# USB_fix.net
KiCad netlist of a schematic drawn in Altium Designer
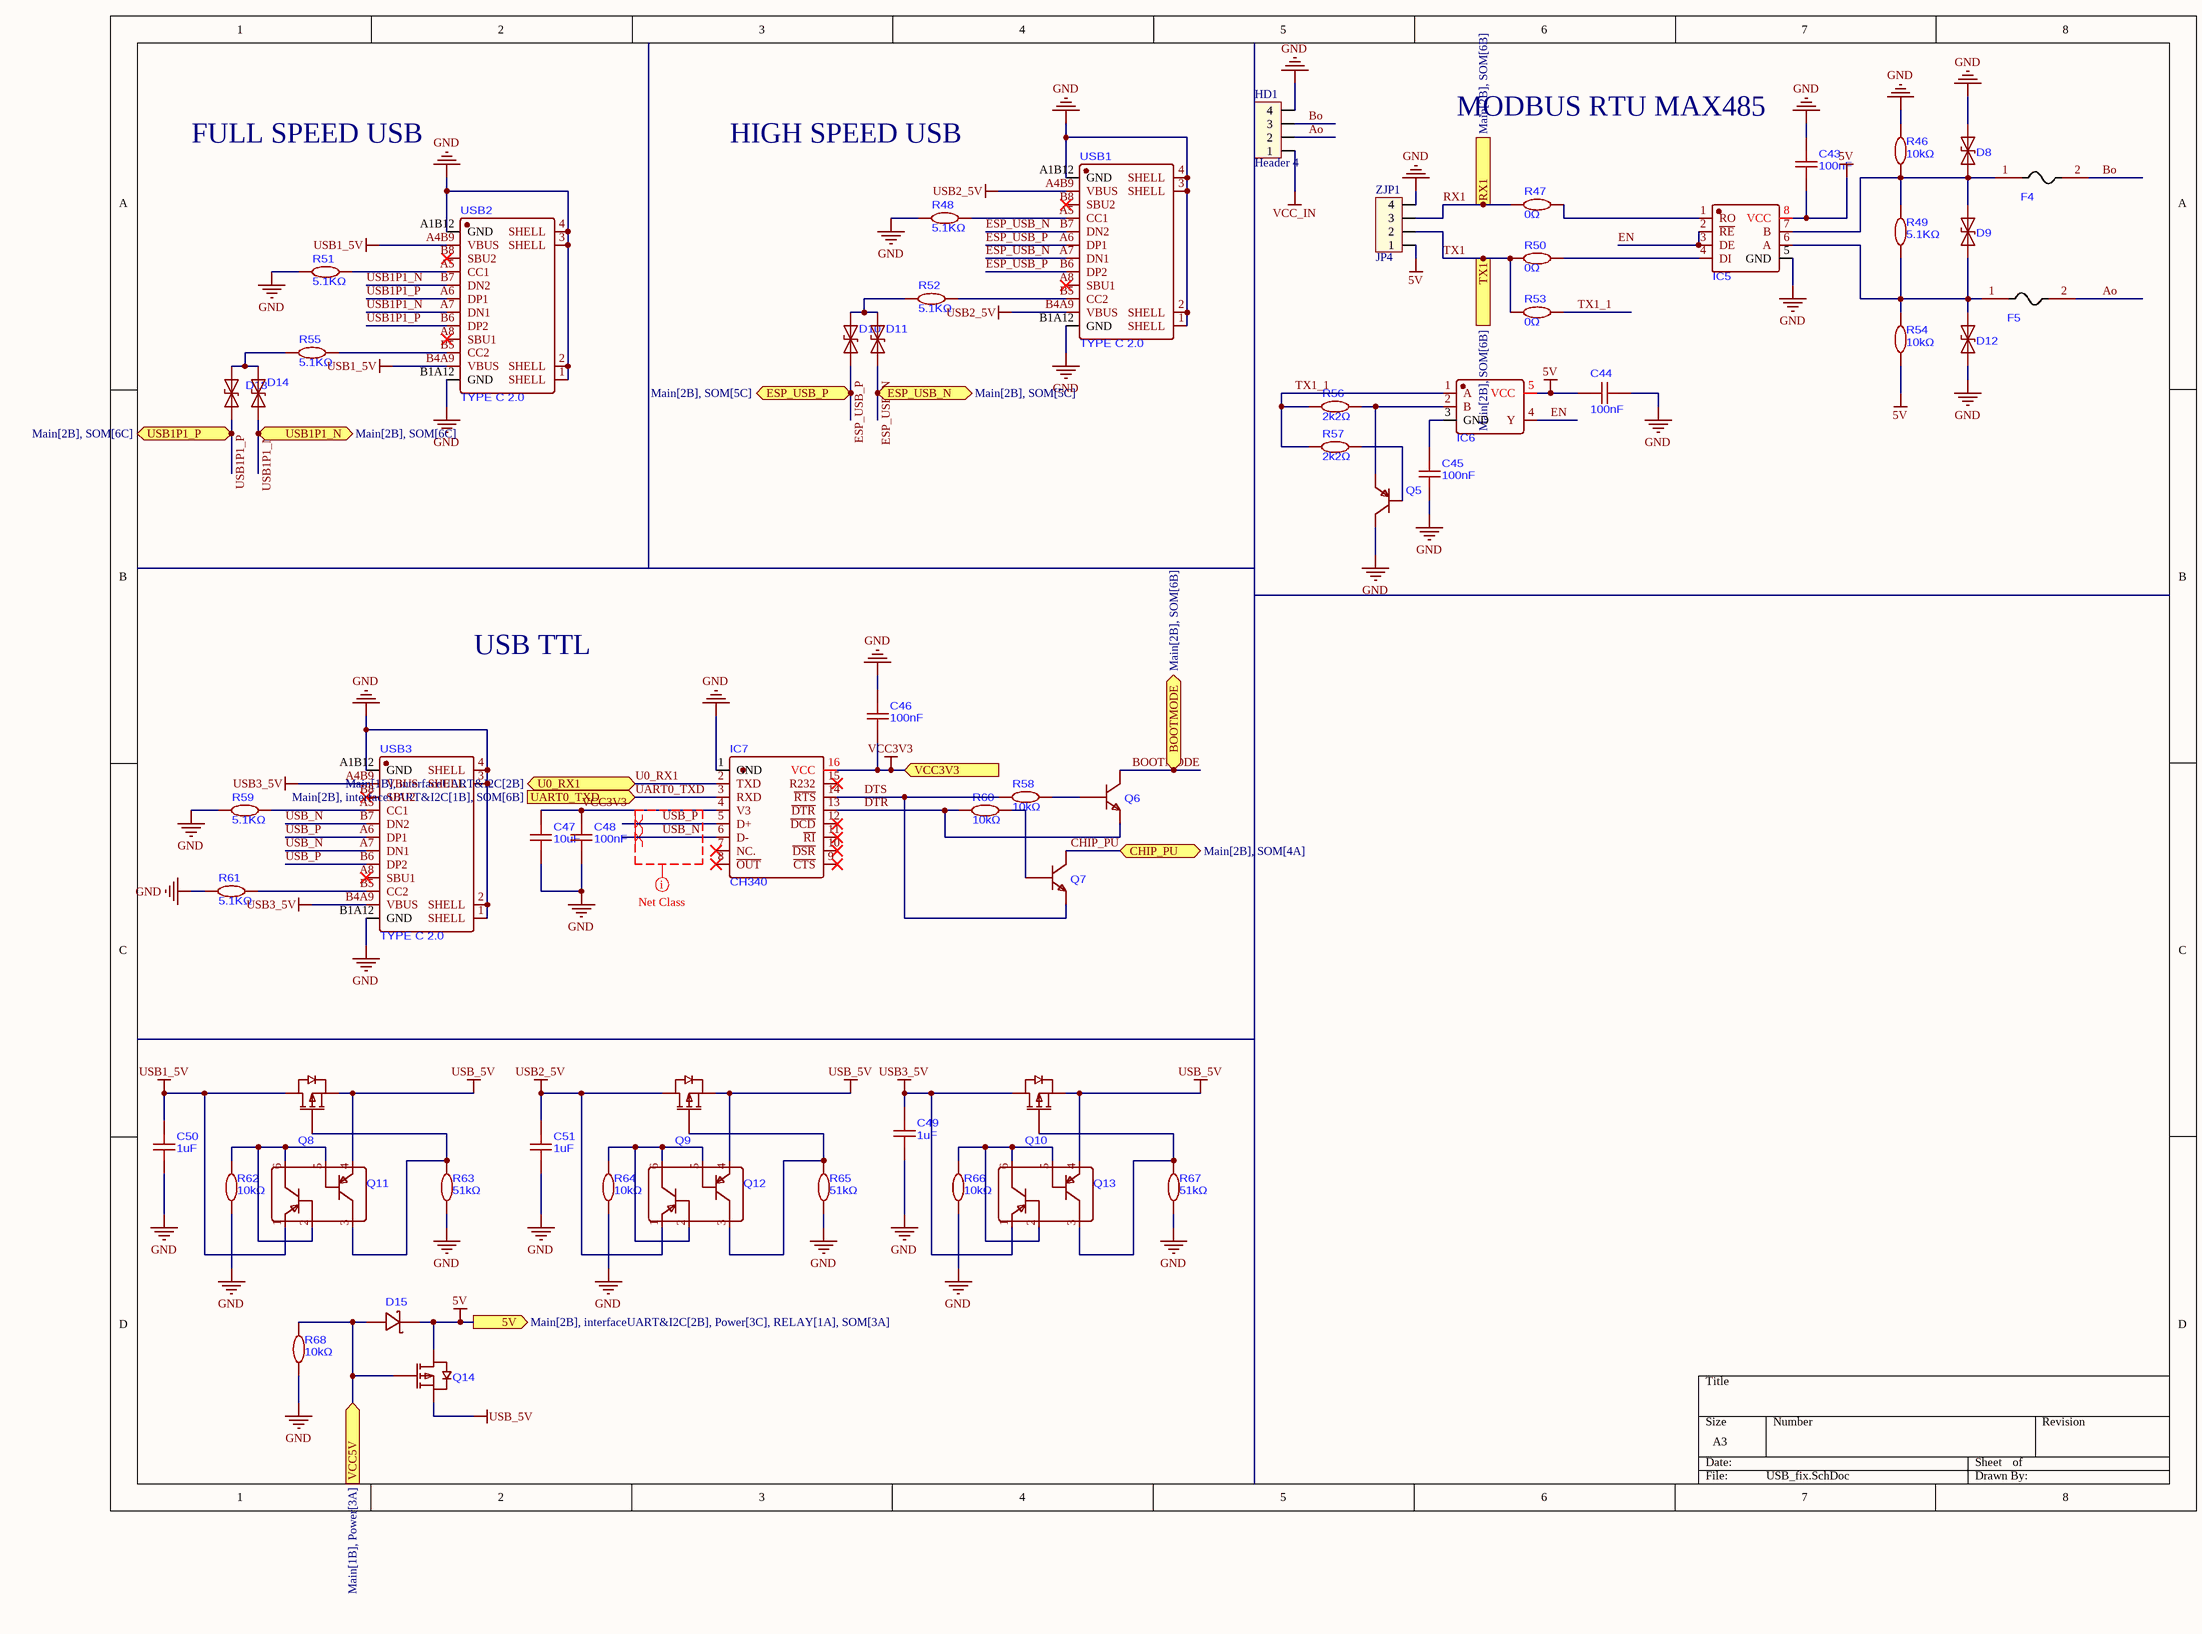
[diagram p0: USB_fix.SchDoc]

(export (version "E")
  (design (tool "Eeschema 10.0.6"))
  (components
    (comp (ref "C43")
      (value "100nF")
      (footprint "C0603")
      (description "50V 100nF X7R ±10% 0603 Ceramic Capacitors ROHS")
      (libsource (lib "Schlib2") (part "CC0603KRX7R9BB104"))
    )
    (comp (ref "C44")
      (value "100nF")
      (footprint "C0603")
      (description "50V 100nF X7R ±10% 0603 Ceramic Capacitors ROHS")
      (libsource (lib "Schlib2") (part "CC0603KRX7R9BB104"))
    )
    (comp (ref "C45")
      (value "100nF")
      (footprint "C0603")
      (description "50V 100nF X7R ±10% 0603 Ceramic Capacitors ROHS")
      (libsource (lib "Schlib2") (part "CC0603KRX7R9BB104"))
    )
    (comp (ref "C46")
      (value "100nF")
      (footprint "C0603")
      (description "50V 100nF X7R ±10% 0603 Ceramic Capacitors ROHS")
      (libsource (lib "Schlib2") (part "CC0603KRX7R9BB104"))
    )
    (comp (ref "C47")
      (value "10uF")
      (footprint "C0603")
      (description "25V 10uF X5R ±20% 0603 Ceramic Capacitors ROHS")
      (libsource (lib "Schlib2") (part "CL10A106MA8NRNC"))
    )
    (comp (ref "C48")
      (value "100nF")
      (footprint "C0603")
      (description "50V 100nF X7R ±10% 0603 Ceramic Capacitors ROHS")
      (libsource (lib "Schlib2") (part "CC0603KRX7R9BB104"))
    )
    (comp (ref "C49")
      (value "1uF")
      (footprint "C0603")
      (description "25V 1uF X7R ±10% 0603 Ceramic Capacitors ROHS")
      (libsource (lib "Schlib2") (part "CL10B105KA8NNNC"))
    )
    (comp (ref "C50")
      (value "1uF")
      (footprint "C0603")
      (description "25V 1uF X7R ±10% 0603 Ceramic Capacitors ROHS")
      (libsource (lib "Schlib2") (part "CL10B105KA8NNNC"))
    )
    (comp (ref "C51")
      (value "1uF")
      (footprint "C0603")
      (description "25V 1uF X7R ±10% 0603 Ceramic Capacitors ROHS")
      (libsource (lib "Schlib2") (part "CL10B105KA8NNNC"))
    )
    (comp (ref "D8")
      (value "TVS DIODE 5VWM 18.6VC SOD-523")
      (footprint "SOD-523_L1.2-W0.8-LS1.6-BI")
      (description "9.4A@8/20us 18.6V 7.8V 5V SOD-523 TVS Diodes RoHS")
      (libsource (lib "Schlib2") (part "LESD5D5.0CT1G"))
    )
    (comp (ref "D9")
      (value "TVS DIODE 5VWM 18.6VC SOD-523")
      (footprint "SOD-523_L1.2-W0.8-LS1.6-BI")
      (description "9.4A@8/20us 18.6V 7.8V 5V SOD-523 TVS Diodes RoHS")
      (libsource (lib "Schlib2") (part "LESD5D5.0CT1G"))
    )
    (comp (ref "D10")
      (value "TVS DIODE 5VWM 18.6VC SOD-523")
      (footprint "SOD-523_L1.2-W0.8-LS1.6-BI")
      (description "9.4A@8/20us 18.6V 7.8V 5V SOD-523 TVS Diodes RoHS")
      (libsource (lib "Schlib2") (part "LESD5D5.0CT1G"))
    )
    (comp (ref "D11")
      (value "TVS DIODE 5VWM 18.6VC SOD-523")
      (footprint "SOD-523_L1.2-W0.8-LS1.6-BI")
      (description "9.4A@8/20us 18.6V 7.8V 5V SOD-523 TVS Diodes RoHS")
      (libsource (lib "Schlib2") (part "LESD5D5.0CT1G"))
    )
    (comp (ref "D12")
      (value "TVS DIODE 5VWM 18.6VC SOD-523")
      (footprint "SOD-523_L1.2-W0.8-LS1.6-BI")
      (description "9.4A@8/20us 18.6V 7.8V 5V SOD-523 TVS Diodes RoHS")
      (libsource (lib "Schlib2") (part "LESD5D5.0CT1G"))
    )
    (comp (ref "D13")
      (value "TVS DIODE 5VWM 18.6VC SOD-523")
      (footprint "SOD-523_L1.2-W0.8-LS1.6-BI")
      (description "9.4A@8/20us 18.6V 7.8V 5V SOD-523 TVS Diodes RoHS")
      (libsource (lib "Schlib2") (part "LESD5D5.0CT1G"))
    )
    (comp (ref "D14")
      (value "TVS DIODE 5VWM 18.6VC SOD-523")
      (footprint "SOD-523_L1.2-W0.8-LS1.6-BI")
      (description "9.4A@8/20us 18.6V 7.8V 5V SOD-523 TVS Diodes RoHS")
      (libsource (lib "Schlib2") (part "LESD5D5.0CT1G"))
    )
    (comp (ref "D15")
      (value "B540CQ-13-F")
      (footprint "SMC_L6.9-W5.9-LS7.9-RD")
      (description "40V 550mV@5A 5A SMC(DO-214AB) Single Diodes ROHS")
      (libsource (lib "Schlib2") (part "B540CQ-13-F"))
    )
    (comp (ref "F4")
      (value "PTC RESET FUSE 24V 100mA 0603")
      (footprint "F0603")
      (description "24V 100mA 40A 300mA 900mΩ 0603 PTC Resettable Fuses RoHS")
      (libsource (lib "Schlib2") (part "0603-010-24V"))
    )
    (comp (ref "F5")
      (value "PTC RESET FUSE 24V 100mA 0603")
      (footprint "F0603")
      (description "24V 100mA 40A 300mA 900mΩ 0603 PTC Resettable Fuses RoHS")
      (libsource (lib "Schlib2") (part "0603-010-24V"))
    )
    (comp (ref "HD1")
      (value "Header 4")
      (footprint "HED4")
      (description "Header 4 (Green)")
      (libsource (lib "syhaunguyen") (part "Hed4"))
    )
    (comp (ref "IC5")
      (value "Low-Power, Slew-Rate-Limited RS-485/RS-422 Transceivers")
      (footprint "SOP-8_L4.9-W3.9-P1.27-LS6.0-BL")
      (description "Transceiver 4.75V~5.25V SOIC-8 Drivers, Receivers, Transceivers RoHS")
      (libsource (lib "Schlib2") (part "MAX485ESA+T_C41365333"))
    )
    (comp (ref "IC6")
      (value "SINGLE 2-INPUT NAND GATE WITH SCHMITT-TRIGGER INPUTS")
      (footprint "SOT-23-5_L3.0-W1.7-P0.95-LS2.8-BL")
      (description "5ns@5V,50pF 10uA 1.65V~5.5V NAND Gate SOT-23-5 Gates and Inverters RoHS")
      (libsource (lib "Schlib2") (part "TP74LVC1G132S5"))
    )
    (comp (ref "IC7")
      (value "CH340")
      (footprint "SOP-16_L10.0-W3.9-P1.27-LS6.0-BL")
      (description "Transceiver USB 2.0 SOP-16 Interface Controllers RoHS")
      (libsource (lib "Schlib2") (part "CH340C"))
    )
    (comp (ref "Q5")
      (value "TRANS PNP 25V 1.5A SOT-23")
      (footprint "SOT-23-3_L2.9-W1.3-P1.90-LS2.4-BR")
      (description "300mW 25V 1.5A PNP SOT-23 Single Bipolar Transistors RoHS")
      (libsource (lib "Schlib2") (part "SS8550_C7420371"))
    )
    (comp (ref "Q6")
      (value "TRANS NPN 25V 0.5A SOT-23")
      (footprint "SOT-23-3_L2.9-W1.3-P1.90-LS2.4-BR")
      (description "300mW 25V 500mA NPN SOT-23 Single Bipolar Transistors RoHS")
      (libsource (lib "Schlib2") (part "S8050_C2828466"))
    )
    (comp (ref "Q7")
      (value "TRANS NPN 25V 0.5A SOT-23")
      (footprint "SOT-23-3_L2.9-W1.3-P1.90-LS2.4-BR")
      (description "300mW 25V 500mA NPN SOT-23 Single Bipolar Transistors RoHS")
      (libsource (lib "Schlib2") (part "S8050_C2828466"))
    )
    (comp (ref "Q8")
      (value "MOSFET P-CH 30V 4.3A SOT-23")
      (footprint "SOT-23-3_L2.9-W1.6-P1.90-LS2.8-BR")
      (description "30V 4.3A 48mΩ@10V 2.5V@250uA 1 P-Channel SOT-23 Single FETs, MOSFETs ROHS")
      (libsource (lib "Schlib2") (part "AO3407A"))
    )
    (comp (ref "Q9")
      (value "MOSFET P-CH 30V 4.3A SOT-23")
      (footprint "SOT-23-3_L2.9-W1.6-P1.90-LS2.8-BR")
      (description "30V 4.3A 48mΩ@10V 2.5V@250uA 1 P-Channel SOT-23 Single FETs, MOSFETs ROHS")
      (libsource (lib "Schlib2") (part "AO3407A"))
    )
    (comp (ref "Q10")
      (value "MOSFET P-CH 30V 4.3A SOT-23")
      (footprint "SOT-23-3_L2.9-W1.6-P1.90-LS2.8-BR")
      (description "30V 4.3A 48mΩ@10V 2.5V@250uA 1 P-Channel SOT-23 Single FETs, MOSFETs ROHS")
      (libsource (lib "Schlib2") (part "AO3407A"))
    )
    (comp (ref "Q11")
      (value "TRANS PNP 40V 200mA SOT-363")
      (footprint "SC-70-6_L2.2-W1.3-P0.65-LS2.1-TL")
      (description "40V 150mW 200mA PNP SOT-363 Single Bipolar Transistors RoHS")
      (libsource (lib "Schlib2") (part "LMBT3906DW1T1"))
    )
    (comp (ref "Q12")
      (value "TRANS PNP 40V 200mA SOT-363")
      (footprint "SC-70-6_L2.2-W1.3-P0.65-LS2.1-TL")
      (description "40V 150mW 200mA PNP SOT-363 Single Bipolar Transistors RoHS")
      (libsource (lib "Schlib2") (part "LMBT3906DW1T1"))
    )
    (comp (ref "Q13")
      (value "TRANS PNP 40V 200mA SOT-363")
      (footprint "SC-70-6_L2.2-W1.3-P0.65-LS2.1-TL")
      (description "40V 150mW 200mA PNP SOT-363 Single Bipolar Transistors RoHS")
      (libsource (lib "Schlib2") (part "LMBT3906DW1T1"))
    )
    (comp (ref "Q14")
      (value "MOSFET P-CH 30V 4.3A SOT-23")
      (footprint "SOT-23-3_L2.9-W1.6-P1.90-LS2.8-BR")
      (description "30V 4.3A 48mΩ@10V 2.5V@250uA 1 P-Channel SOT-23 Single FETs, MOSFETs ROHS")
      (libsource (lib "Schlib2") (part "AO3407A"))
    )
    (comp (ref "R46")
      (value "10kΩ")
      (footprint "R0603")
      (description "100mW 10kΩ 75V ±100ppm/℃ Thick Film Resistor ±1% 0603 Chip Resistor - Surface Mount ROHS")
      (libsource (lib "Schlib2") (part "RC0603FR-0710KL"))
    )
    (comp (ref "R47")
      (value "0Ω")
      (footprint "R0603")
      (description "100mW 0Ω 75V Thick Film Resistor ±5% 0603 Chip Resistor - Surface Mount RoHS")
      (libsource (lib "Schlib2") (part "RC0603JR-070RL"))
    )
    (comp (ref "R48")
      (value "5.1KΩ")
      (footprint "R0603")
      (description "100mW 5.1kΩ 75V ±100ppm/℃ Thick Film Resistor ±1% 0603 Chip Resistor - Surface Mount RoHS")
      (libsource (lib "Schlib2") (part "FRC0603F5101TS"))
    )
    (comp (ref "R49")
      (value "5.1KΩ")
      (footprint "R0603")
      (description "100mW 5.1kΩ 75V ±100ppm/℃ Thick Film Resistor ±1% 0603 Chip Resistor - Surface Mount RoHS")
      (libsource (lib "Schlib2") (part "FRC0603F5101TS"))
    )
    (comp (ref "R50")
      (value "0Ω")
      (footprint "R0603")
      (description "100mW 0Ω 75V Thick Film Resistor ±5% 0603 Chip Resistor - Surface Mount RoHS")
      (libsource (lib "Schlib2") (part "RC0603JR-070RL"))
    )
    (comp (ref "R51")
      (value "5.1KΩ")
      (footprint "R0603")
      (description "100mW 5.1kΩ 75V ±100ppm/℃ Thick Film Resistor ±1% 0603 Chip Resistor - Surface Mount RoHS")
      (libsource (lib "Schlib2") (part "FRC0603F5101TS"))
    )
    (comp (ref "R52")
      (value "5.1KΩ")
      (footprint "R0603")
      (description "100mW 5.1kΩ 75V ±100ppm/℃ Thick Film Resistor ±1% 0603 Chip Resistor - Surface Mount RoHS")
      (libsource (lib "Schlib2") (part "FRC0603F5101TS"))
    )
    (comp (ref "R53")
      (value "0Ω")
      (footprint "R0603")
      (description "100mW 0Ω 75V Thick Film Resistor ±5% 0603 Chip Resistor - Surface Mount RoHS")
      (libsource (lib "Schlib2") (part "RC0603JR-070RL"))
    )
    (comp (ref "R54")
      (value "10kΩ")
      (footprint "R0603")
      (description "100mW 10kΩ 75V ±100ppm/℃ Thick Film Resistor ±1% 0603 Chip Resistor - Surface Mount ROHS")
      (libsource (lib "Schlib2") (part "RC0603FR-0710KL"))
    )
    (comp (ref "R55")
      (value "5.1KΩ")
      (footprint "R0603")
      (description "100mW 5.1kΩ 75V ±100ppm/℃ Thick Film Resistor ±1% 0603 Chip Resistor - Surface Mount RoHS")
      (libsource (lib "Schlib2") (part "FRC0603F5101TS"))
    )
    (comp (ref "R56")
      (value "2k2Ω")
      (footprint "R0603")
      (description "100mW 2.2kΩ 75V ±100ppm/℃ Thick Film Resistor ±1% 0603 Chip Resistor - Surface Mount RoHS")
      (libsource (lib "Schlib2") (part "RC0603FR-072K2L"))
    )
    (comp (ref "R57")
      (value "2k2Ω")
      (footprint "R0603")
      (description "100mW 2.2kΩ 75V ±100ppm/℃ Thick Film Resistor ±1% 0603 Chip Resistor - Surface Mount RoHS")
      (libsource (lib "Schlib2") (part "RC0603FR-072K2L"))
    )
    (comp (ref "R58")
      (value "10kΩ")
      (footprint "R0603")
      (description "100mW 10kΩ 75V ±100ppm/℃ Thick Film Resistor ±1% 0603 Chip Resistor - Surface Mount ROHS")
      (libsource (lib "Schlib2") (part "RC0603FR-0710KL"))
    )
    (comp (ref "R59")
      (value "5.1KΩ")
      (footprint "R0603")
      (description "100mW 5.1kΩ 75V ±100ppm/℃ Thick Film Resistor ±1% 0603 Chip Resistor - Surface Mount RoHS")
      (libsource (lib "Schlib2") (part "FRC0603F5101TS"))
    )
    (comp (ref "R60")
      (value "10kΩ")
      (footprint "R0603")
      (description "100mW 10kΩ 75V ±100ppm/℃ Thick Film Resistor ±1% 0603 Chip Resistor - Surface Mount ROHS")
      (libsource (lib "Schlib2") (part "RC0603FR-0710KL"))
    )
    (comp (ref "R61")
      (value "5.1KΩ")
      (footprint "R0603")
      (description "100mW 5.1kΩ 75V ±100ppm/℃ Thick Film Resistor ±1% 0603 Chip Resistor - Surface Mount RoHS")
      (libsource (lib "Schlib2") (part "FRC0603F5101TS"))
    )
    (comp (ref "R62")
      (value "10kΩ")
      (footprint "R0603")
      (description "100mW 10kΩ 75V ±100ppm/℃ Thick Film Resistor ±1% 0603 Chip Resistor - Surface Mount ROHS")
      (libsource (lib "Schlib2") (part "RC0603FR-0710KL"))
    )
    (comp (ref "R63")
      (value "51kΩ")
      (footprint "R0603")
      (description "100mW 51kΩ 75V ±100ppm/℃ Thick Film Resistor ±1% 0603 Chip Resistor - Surface Mount RoHS")
      (libsource (lib "Schlib2") (part "RC0603FR-07100KL_1RC0603FR-0751KL"))
    )
    (comp (ref "R64")
      (value "10kΩ")
      (footprint "R0603")
      (description "100mW 10kΩ 75V ±100ppm/℃ Thick Film Resistor ±1% 0603 Chip Resistor - Surface Mount ROHS")
      (libsource (lib "Schlib2") (part "RC0603FR-0710KL"))
    )
    (comp (ref "R65")
      (value "51kΩ")
      (footprint "R0603")
      (description "100mW 51kΩ 75V ±100ppm/℃ Thick Film Resistor ±1% 0603 Chip Resistor - Surface Mount RoHS")
      (libsource (lib "Schlib2") (part "RC0603FR-07100KL_1RC0603FR-0751KL"))
    )
    (comp (ref "R66")
      (value "10kΩ")
      (footprint "R0603")
      (description "100mW 10kΩ 75V ±100ppm/℃ Thick Film Resistor ±1% 0603 Chip Resistor - Surface Mount ROHS")
      (libsource (lib "Schlib2") (part "RC0603FR-0710KL"))
    )
    (comp (ref "R67")
      (value "51kΩ")
      (footprint "R0603")
      (description "100mW 51kΩ 75V ±100ppm/℃ Thick Film Resistor ±1% 0603 Chip Resistor - Surface Mount RoHS")
      (libsource (lib "Schlib2") (part "RC0603FR-07100KL_1RC0603FR-0751KL"))
    )
    (comp (ref "R68")
      (value "10kΩ")
      (footprint "R0603")
      (description "100mW 10kΩ 75V ±100ppm/℃ Thick Film Resistor ±1% 0603 Chip Resistor - Surface Mount ROHS")
      (libsource (lib "Schlib2") (part "RC0603FR-0710KL"))
    )
    (comp (ref "USB1")
      (value "TYPE C 2.0")
      (footprint "USB-C-SMD_G-SWITCH_GT-USB-7010ASV")
      (description "USB 2.0 1 16P -40℃~+85℃ Type-C SMD USB, DVI, HDMI Connector Assemblies RoHS")
      (libsource (lib "Schlib2") (part "GT-USB-7010ASV"))
    )
    (comp (ref "USB2")
      (value "TYPE C 2.0")
      (footprint "USB-C-SMD_G-SWITCH_GT-USB-7010ASV")
      (description "USB 2.0 1 16P -40℃~+85℃ Type-C SMD USB, DVI, HDMI Connector Assemblies RoHS")
      (libsource (lib "Schlib2") (part "GT-USB-7010ASV"))
    )
    (comp (ref "USB3")
      (value "TYPE C 2.0")
      (footprint "USB-C-SMD_G-SWITCH_GT-USB-7010ASV")
      (description "USB 2.0 1 16P -40℃~+85℃ Type-C SMD USB, DVI, HDMI Connector Assemblies RoHS")
      (libsource (lib "Schlib2") (part "GT-USB-7010ASV"))
    )
    (comp (ref "ZJP1")
      (value "JP4")
      (footprint "CON4")
      (description "Connector 4")
      (libsource (lib "syhaunguyen") (part "Con4"))
    )
  )
  (nets
    (net (code "1") (name "/Ao") (class "Default")
      (node (ref "F5") (pin "2") (pinfunction "2_2") (pintype "passive"))
      (node (ref "HD1") (pin "2") (pinfunction "2_2") (pintype "passive"))
    )
    (net (code "2") (name "/BOOTMODE") (class "Default")
      (node (ref "Q6") (pin "3") (pinfunction "C_3") (pintype "passive"))
    )
    (net (code "3") (name "/Bo") (class "Default")
      (node (ref "F4") (pin "2") (pinfunction "2_2") (pintype "passive"))
      (node (ref "HD1") (pin "3") (pinfunction "3_3") (pintype "passive"))
    )
    (net (code "4") (name "/CHIP_PU") (class "Default")
      (node (ref "Q7") (pin "3") (pinfunction "C_3") (pintype "passive"))
    )
    (net (code "5") (name "/DTR") (class "Default")
      (node (ref "IC7") (pin "13") (pinfunction "~{DTR}_13") (pintype "passive"))
      (node (ref "Q6") (pin "2") (pinfunction "E_2") (pintype "passive"))
      (node (ref "R60") (pin "1") (pinfunction "1_1") (pintype "passive"))
    )
    (net (code "6") (name "/DTS") (class "Default")
      (node (ref "IC7") (pin "14") (pinfunction "~{RTS}_14") (pintype "passive"))
      (node (ref "Q7") (pin "2") (pinfunction "E_2") (pintype "passive"))
      (node (ref "R58") (pin "1") (pinfunction "1_1") (pintype "passive"))
    )
    (net (code "7") (name "/EN") (class "Default")
      (node (ref "IC5") (pin "2") (pinfunction "~{RE}_2") (pintype "passive"))
      (node (ref "IC5") (pin "3") (pinfunction "DE_3") (pintype "passive"))
      (node (ref "IC6") (pin "4") (pinfunction "Y_4") (pintype "passive"))
    )
    (net (code "8") (name "/ESP_USB_N") (class "Default")
      (node (ref "D11") (pin "1") (pinfunction "K_1") (pintype "passive"))
      (node (ref "USB1") (pin "A7") (pinfunction "DN1_A7") (pintype "passive"))
      (node (ref "USB1") (pin "B7") (pinfunction "DN2_B7") (pintype "passive"))
    )
    (net (code "9") (name "/ESP_USB_P") (class "Default")
      (node (ref "D10") (pin "1") (pinfunction "K_1") (pintype "passive"))
      (node (ref "USB1") (pin "A6") (pinfunction "DP1_A6") (pintype "passive"))
      (node (ref "USB1") (pin "B6") (pinfunction "DP2_B6") (pintype "passive"))
    )
    (net (code "10") (name "/RX1") (class "Default")
      (node (ref "R47") (pin "1") (pinfunction "1_1") (pintype "passive"))
      (node (ref "ZJP1") (pin "3") (pinfunction "3_3") (pintype "passive"))
    )
    (net (code "11") (name "/TX1") (class "Default")
      (node (ref "R50") (pin "1") (pinfunction "1_1") (pintype "passive"))
      (node (ref "R53") (pin "1") (pinfunction "1_1") (pintype "passive"))
      (node (ref "ZJP1") (pin "2") (pinfunction "2_2") (pintype "passive"))
    )
    (net (code "12") (name "/TX1_1") (class "Default")
      (node (ref "IC6") (pin "1") (pinfunction "A_1") (pintype "passive"))
      (node (ref "R53") (pin "2") (pinfunction "2_2") (pintype "passive"))
      (node (ref "R56") (pin "2") (pinfunction "2_2") (pintype "passive"))
      (node (ref "R57") (pin "1") (pinfunction "1_1") (pintype "passive"))
    )
    (net (code "13") (name "/U0_RX1") (class "Default")
      (node (ref "IC7") (pin "2") (pinfunction "TXD_2") (pintype "passive"))
    )
    (net (code "14") (name "/UART0_TXD") (class "Default")
      (node (ref "IC7") (pin "3") (pinfunction "RXD_3") (pintype "passive"))
    )
    (net (code "15") (name "/USB1P1_N") (class "Default")
      (node (ref "D14") (pin "1") (pinfunction "K_1") (pintype "passive"))
      (node (ref "USB2") (pin "A7") (pinfunction "DN1_A7") (pintype "passive"))
      (node (ref "USB2") (pin "B7") (pinfunction "DN2_B7") (pintype "passive"))
    )
    (net (code "16") (name "/USB1P1_P") (class "Default")
      (node (ref "D13") (pin "1") (pinfunction "K_1") (pintype "passive"))
      (node (ref "USB2") (pin "A6") (pinfunction "DP1_A6") (pintype "passive"))
      (node (ref "USB2") (pin "B6") (pinfunction "DP2_B6") (pintype "passive"))
    )
    (net (code "17") (name "/USB_N") (class "Default")
      (node (ref "IC7") (pin "6") (pinfunction "D-_6") (pintype "passive"))
      (node (ref "USB3") (pin "A7") (pinfunction "DN1_A7") (pintype "passive"))
      (node (ref "USB3") (pin "B7") (pinfunction "DN2_B7") (pintype "passive"))
    )
    (net (code "18") (name "/USB_P") (class "Default")
      (node (ref "IC7") (pin "5") (pinfunction "D+_5") (pintype "passive"))
      (node (ref "USB3") (pin "A6") (pinfunction "DP1_A6") (pintype "passive"))
      (node (ref "USB3") (pin "B6") (pinfunction "DP2_B6") (pintype "passive"))
    )
    (net (code "19") (name "/VCC5V") (class "Default")
      (node (ref "D15") (pin "2") (pinfunction "A_2") (pintype "passive"))
      (node (ref "Q14") (pin "1") (pinfunction "G_1") (pintype "passive"))
      (node (ref "R68") (pin "2") (pinfunction "2_2") (pintype "passive"))
    )
    (net (code "20") (name "5V") (class "Default")
      (node (ref "C43") (pin "1") (pinfunction "1_1") (pintype "passive"))
      (node (ref "C44") (pin "2") (pinfunction "2_2") (pintype "passive"))
      (node (ref "D15") (pin "1") (pinfunction "C_1") (pintype "passive"))
      (node (ref "IC5") (pin "8") (pinfunction "VCC_8") (pintype "passive"))
      (node (ref "IC6") (pin "5") (pinfunction "VCC_5") (pintype "passive"))
      (node (ref "Q14") (pin "3") (pinfunction "D_3") (pintype "passive"))
      (node (ref "R54") (pin "1") (pinfunction "1_1") (pintype "passive"))
      (node (ref "ZJP1") (pin "1") (pinfunction "1_1") (pintype "passive"))
    )
    (net (code "21") (name "GND") (class "Default")
      (node (ref "C43") (pin "2") (pinfunction "2_2") (pintype "passive"))
      (node (ref "C44") (pin "1") (pinfunction "1_1") (pintype "passive"))
      (node (ref "C45") (pin "1") (pinfunction "1_1") (pintype "passive"))
      (node (ref "C46") (pin "2") (pinfunction "2_2") (pintype "passive"))
      (node (ref "C47") (pin "1") (pinfunction "1_1") (pintype "passive"))
      (node (ref "C48") (pin "1") (pinfunction "1_1") (pintype "passive"))
      (node (ref "C49") (pin "1") (pinfunction "1_1") (pintype "passive"))
      (node (ref "C50") (pin "1") (pinfunction "1_1") (pintype "passive"))
      (node (ref "C51") (pin "1") (pinfunction "1_1") (pintype "passive"))
      (node (ref "D12") (pin "1") (pinfunction "K_1") (pintype "passive"))
      (node (ref "D8") (pin "2") (pinfunction "A_2") (pintype "passive"))
      (node (ref "HD1") (pin "4") (pinfunction "4_4") (pintype "passive"))
      (node (ref "IC5") (pin "5") (pinfunction "GND_5") (pintype "passive"))
      (node (ref "IC7") (pin "1") (pinfunction "GND_1") (pintype "passive"))
      (node (ref "Q5") (pin "3") (pinfunction "C_3") (pintype "passive"))
      (node (ref "R46") (pin "2") (pinfunction "2_2") (pintype "passive"))
      (node (ref "R48") (pin "1") (pinfunction "1_1") (pintype "passive"))
      (node (ref "R51") (pin "1") (pinfunction "1_1") (pintype "passive"))
      (node (ref "R59") (pin "1") (pinfunction "1_1") (pintype "passive"))
      (node (ref "R61") (pin "1") (pinfunction "1_1") (pintype "passive"))
      (node (ref "R62") (pin "1") (pinfunction "1_1") (pintype "passive"))
      (node (ref "R63") (pin "1") (pinfunction "1_1") (pintype "passive"))
      (node (ref "R64") (pin "1") (pinfunction "1_1") (pintype "passive"))
      (node (ref "R65") (pin "1") (pinfunction "1_1") (pintype "passive"))
      (node (ref "R66") (pin "1") (pinfunction "1_1") (pintype "passive"))
      (node (ref "R67") (pin "1") (pinfunction "1_1") (pintype "passive"))
      (node (ref "R68") (pin "1") (pinfunction "1_1") (pintype "passive"))
      (node (ref "USB1") (pin "1") (pinfunction "SHELL_1") (pintype "passive"))
      (node (ref "USB1") (pin "2") (pinfunction "SHELL_2") (pintype "passive"))
      (node (ref "USB1") (pin "3") (pinfunction "SHELL_3") (pintype "passive"))
      (node (ref "USB1") (pin "4") (pinfunction "SHELL_4") (pintype "passive"))
      (node (ref "USB1") (pin "A1B12") (pinfunction "GND_A1B12") (pintype "passive"))
      (node (ref "USB1") (pin "B1A12") (pinfunction "GND_B1A12") (pintype "passive"))
      (node (ref "USB2") (pin "1") (pinfunction "SHELL_1") (pintype "passive"))
      (node (ref "USB2") (pin "2") (pinfunction "SHELL_2") (pintype "passive"))
      (node (ref "USB2") (pin "3") (pinfunction "SHELL_3") (pintype "passive"))
      (node (ref "USB2") (pin "4") (pinfunction "SHELL_4") (pintype "passive"))
      (node (ref "USB2") (pin "A1B12") (pinfunction "GND_A1B12") (pintype "passive"))
      (node (ref "USB2") (pin "B1A12") (pinfunction "GND_B1A12") (pintype "passive"))
      (node (ref "USB3") (pin "1") (pinfunction "SHELL_1") (pintype "passive"))
      (node (ref "USB3") (pin "2") (pinfunction "SHELL_2") (pintype "passive"))
      (node (ref "USB3") (pin "3") (pinfunction "SHELL_3") (pintype "passive"))
      (node (ref "USB3") (pin "4") (pinfunction "SHELL_4") (pintype "passive"))
      (node (ref "USB3") (pin "A1B12") (pinfunction "GND_A1B12") (pintype "passive"))
      (node (ref "USB3") (pin "B1A12") (pinfunction "GND_B1A12") (pintype "passive"))
      (node (ref "ZJP1") (pin "4") (pinfunction "4_4") (pintype "passive"))
    )
    (net (code "22") (name "Net-(D8-K)") (class "Default")
      (node (ref "D8") (pin "1") (pinfunction "K_1") (pintype "passive"))
      (node (ref "D9") (pin "2") (pinfunction "A_2") (pintype "passive"))
      (node (ref "F4") (pin "1") (pinfunction "1_1") (pintype "passive"))
      (node (ref "IC5") (pin "7") (pinfunction "B_7") (pintype "passive"))
      (node (ref "R46") (pin "1") (pinfunction "1_1") (pintype "passive"))
      (node (ref "R49") (pin "2") (pinfunction "2_2") (pintype "passive"))
    )
    (net (code "23") (name "Net-(D10-A)") (class "Default")
      (node (ref "D10") (pin "2") (pinfunction "A_2") (pintype "passive"))
      (node (ref "D11") (pin "2") (pinfunction "A_2") (pintype "passive"))
      (node (ref "R52") (pin "1") (pinfunction "1_1") (pintype "passive"))
    )
    (net (code "24") (name "Net-(D12-A)") (class "Default")
      (node (ref "D12") (pin "2") (pinfunction "A_2") (pintype "passive"))
      (node (ref "D9") (pin "1") (pinfunction "K_1") (pintype "passive"))
      (node (ref "F5") (pin "1") (pinfunction "1_1") (pintype "passive"))
      (node (ref "IC5") (pin "6") (pinfunction "A_6") (pintype "passive"))
      (node (ref "R49") (pin "1") (pinfunction "1_1") (pintype "passive"))
      (node (ref "R54") (pin "2") (pinfunction "2_2") (pintype "passive"))
    )
    (net (code "25") (name "Net-(D13-A)") (class "Default")
      (node (ref "D13") (pin "2") (pinfunction "A_2") (pintype "passive"))
      (node (ref "D14") (pin "2") (pinfunction "A_2") (pintype "passive"))
      (node (ref "R55") (pin "1") (pinfunction "1_1") (pintype "passive"))
    )
    (net (code "26") (name "Net-(IC5-DI)") (class "Default")
      (node (ref "IC5") (pin "4") (pinfunction "DI_4") (pintype "passive"))
      (node (ref "R50") (pin "2") (pinfunction "2_2") (pintype "passive"))
    )
    (net (code "27") (name "Net-(IC5-RO)") (class "Default")
      (node (ref "IC5") (pin "1") (pinfunction "RO_1") (pintype "passive"))
      (node (ref "R47") (pin "2") (pinfunction "2_2") (pintype "passive"))
    )
    (net (code "28") (name "Net-(IC6-B)") (class "Default")
      (node (ref "IC6") (pin "2") (pinfunction "B_2") (pintype "passive"))
      (node (ref "Q5") (pin "2") (pinfunction "E_2") (pintype "passive"))
      (node (ref "R56") (pin "1") (pinfunction "1_1") (pintype "passive"))
    )
    (net (code "29") (name "Net-(IC6-GND)") (class "Default")
      (node (ref "C45") (pin "2") (pinfunction "2_2") (pintype "passive"))
      (node (ref "IC6") (pin "3") (pinfunction "GND_3") (pintype "passive"))
    )
    (net (code "30") (name "Net-(Q5-B)") (class "Default")
      (node (ref "Q5") (pin "1") (pinfunction "B_1") (pintype "passive"))
      (node (ref "R57") (pin "2") (pinfunction "2_2") (pintype "passive"))
    )
    (net (code "31") (name "Net-(Q6-B)") (class "Default")
      (node (ref "Q6") (pin "1") (pinfunction "B_1") (pintype "passive"))
      (node (ref "R58") (pin "2") (pinfunction "2_2") (pintype "passive"))
    )
    (net (code "32") (name "Net-(Q7-B)") (class "Default")
      (node (ref "Q7") (pin "1") (pinfunction "B_1") (pintype "passive"))
      (node (ref "R60") (pin "2") (pinfunction "2_2") (pintype "passive"))
    )
    (net (code "33") (name "Net-(Q10-G)") (class "Default")
      (node (ref "Q10") (pin "1") (pinfunction "G_1") (pintype "passive"))
      (node (ref "Q13") (pin "3") (pinfunction "C1_3") (pintype "passive"))
      (node (ref "R67") (pin "2") (pinfunction "2_2") (pintype "passive"))
    )
    (net (code "34") (name "Net-(Q11-B1)") (class "Default")
      (node (ref "Q11") (pin "2") (pinfunction "B2_2") (pintype "passive"))
      (node (ref "Q11") (pin "5") (pinfunction "B1_5") (pintype "passive"))
      (node (ref "Q11") (pin "6") (pinfunction "C2_6") (pintype "passive"))
      (node (ref "R62") (pin "2") (pinfunction "2_2") (pintype "passive"))
    )
    (net (code "35") (name "Net-(Q11-C1)") (class "Default")
      (node (ref "Q11") (pin "3") (pinfunction "C1_3") (pintype "passive"))
      (node (ref "Q8") (pin "1") (pinfunction "G_1") (pintype "passive"))
      (node (ref "R63") (pin "2") (pinfunction "2_2") (pintype "passive"))
    )
    (net (code "36") (name "Net-(Q12-B1)") (class "Default")
      (node (ref "Q12") (pin "2") (pinfunction "B2_2") (pintype "passive"))
      (node (ref "Q12") (pin "5") (pinfunction "B1_5") (pintype "passive"))
      (node (ref "Q12") (pin "6") (pinfunction "C2_6") (pintype "passive"))
      (node (ref "R64") (pin "2") (pinfunction "2_2") (pintype "passive"))
    )
    (net (code "37") (name "Net-(Q12-C1)") (class "Default")
      (node (ref "Q12") (pin "3") (pinfunction "C1_3") (pintype "passive"))
      (node (ref "Q9") (pin "1") (pinfunction "G_1") (pintype "passive"))
      (node (ref "R65") (pin "2") (pinfunction "2_2") (pintype "passive"))
    )
    (net (code "38") (name "Net-(Q13-B1)") (class "Default")
      (node (ref "Q13") (pin "2") (pinfunction "B2_2") (pintype "passive"))
      (node (ref "Q13") (pin "5") (pinfunction "B1_5") (pintype "passive"))
      (node (ref "Q13") (pin "6") (pinfunction "C2_6") (pintype "passive"))
      (node (ref "R66") (pin "2") (pinfunction "2_2") (pintype "passive"))
    )
    (net (code "39") (name "Net-(USB1-CC1)") (class "Default")
      (node (ref "R48") (pin "2") (pinfunction "2_2") (pintype "passive"))
      (node (ref "USB1") (pin "A5") (pinfunction "CC1_A5") (pintype "passive"))
    )
    (net (code "40") (name "Net-(USB1-CC2)") (class "Default")
      (node (ref "R52") (pin "2") (pinfunction "2_2") (pintype "passive"))
      (node (ref "USB1") (pin "B5") (pinfunction "CC2_B5") (pintype "passive"))
    )
    (net (code "41") (name "Net-(USB2-CC1)") (class "Default")
      (node (ref "R51") (pin "2") (pinfunction "2_2") (pintype "passive"))
      (node (ref "USB2") (pin "A5") (pinfunction "CC1_A5") (pintype "passive"))
    )
    (net (code "42") (name "Net-(USB2-CC2)") (class "Default")
      (node (ref "R55") (pin "2") (pinfunction "2_2") (pintype "passive"))
      (node (ref "USB2") (pin "B5") (pinfunction "CC2_B5") (pintype "passive"))
    )
    (net (code "43") (name "Net-(USB3-CC1)") (class "Default")
      (node (ref "R59") (pin "2") (pinfunction "2_2") (pintype "passive"))
      (node (ref "USB3") (pin "A5") (pinfunction "CC1_A5") (pintype "passive"))
    )
    (net (code "44") (name "Net-(USB3-CC2)") (class "Default")
      (node (ref "R61") (pin "2") (pinfunction "2_2") (pintype "passive"))
      (node (ref "USB3") (pin "B5") (pinfunction "CC2_B5") (pintype "passive"))
    )
    (net (code "45") (name "USB1_5V") (class "Default")
      (node (ref "C50") (pin "2") (pinfunction "2_2") (pintype "passive"))
      (node (ref "Q11") (pin "1") (pinfunction "E2_1") (pintype "passive"))
      (node (ref "Q8") (pin "3") (pinfunction "D_3") (pintype "passive"))
      (node (ref "USB2") (pin "A4B9") (pinfunction "VBUS_A4B9") (pintype "passive"))
      (node (ref "USB2") (pin "B4A9") (pinfunction "VBUS_B4A9") (pintype "passive"))
    )
    (net (code "46") (name "USB2_5V") (class "Default")
      (node (ref "C51") (pin "2") (pinfunction "2_2") (pintype "passive"))
      (node (ref "Q12") (pin "1") (pinfunction "E2_1") (pintype "passive"))
      (node (ref "Q9") (pin "3") (pinfunction "D_3") (pintype "passive"))
      (node (ref "USB1") (pin "A4B9") (pinfunction "VBUS_A4B9") (pintype "passive"))
      (node (ref "USB1") (pin "B4A9") (pinfunction "VBUS_B4A9") (pintype "passive"))
    )
    (net (code "47") (name "USB3_5V") (class "Default")
      (node (ref "C49") (pin "2") (pinfunction "2_2") (pintype "passive"))
      (node (ref "Q10") (pin "3") (pinfunction "D_3") (pintype "passive"))
      (node (ref "Q13") (pin "1") (pinfunction "E2_1") (pintype "passive"))
      (node (ref "USB3") (pin "A4B9") (pinfunction "VBUS_A4B9") (pintype "passive"))
      (node (ref "USB3") (pin "B4A9") (pinfunction "VBUS_B4A9") (pintype "passive"))
    )
    (net (code "48") (name "USB_5V") (class "Default")
      (node (ref "Q10") (pin "2") (pinfunction "S_2") (pintype "passive"))
      (node (ref "Q11") (pin "4") (pinfunction "E1_4") (pintype "passive"))
      (node (ref "Q12") (pin "4") (pinfunction "E1_4") (pintype "passive"))
      (node (ref "Q13") (pin "4") (pinfunction "E1_4") (pintype "passive"))
      (node (ref "Q14") (pin "2") (pinfunction "S_2") (pintype "passive"))
      (node (ref "Q8") (pin "2") (pinfunction "S_2") (pintype "passive"))
      (node (ref "Q9") (pin "2") (pinfunction "S_2") (pintype "passive"))
    )
    (net (code "49") (name "VCC3V3") (class "Default")
      (node (ref "C46") (pin "1") (pinfunction "1_1") (pintype "passive"))
      (node (ref "C47") (pin "2") (pinfunction "2_2") (pintype "passive"))
      (node (ref "C48") (pin "2") (pinfunction "2_2") (pintype "passive"))
      (node (ref "IC7") (pin "16") (pinfunction "VCC_16") (pintype "passive"))
      (node (ref "IC7") (pin "4") (pinfunction "V3_4") (pintype "passive"))
    )
    (net (code "50") (name "VCC_IN") (class "Default")
      (node (ref "HD1") (pin "1") (pinfunction "1_1") (pintype "passive"))
    )
    (net (code "51") (name "unconnected-(IC7-NC.-Pad7)") (class "Default")
      (node (ref "IC7") (pin "7") (pinfunction "NC._7") (pintype "passive+no_connect"))
    )
    (net (code "52") (name "unconnected-(IC7-R232-Pad15)") (class "Default")
      (node (ref "IC7") (pin "15") (pinfunction "R232_15") (pintype "passive+no_connect"))
    )
    (net (code "53") (name "unconnected-(IC7-~{CTS}-Pad9)") (class "Default")
      (node (ref "IC7") (pin "9") (pinfunction "~{CTS}_9") (pintype "passive+no_connect"))
    )
    (net (code "54") (name "unconnected-(IC7-~{DCD}-Pad12)") (class "Default")
      (node (ref "IC7") (pin "12") (pinfunction "~{DCD}_12") (pintype "passive+no_connect"))
    )
    (net (code "55") (name "unconnected-(IC7-~{DSR}-Pad10)") (class "Default")
      (node (ref "IC7") (pin "10") (pinfunction "~{DSR}_10") (pintype "passive+no_connect"))
    )
    (net (code "56") (name "unconnected-(IC7-~{OUT}-Pad8)") (class "Default")
      (node (ref "IC7") (pin "8") (pinfunction "~{OUT}_8") (pintype "passive+no_connect"))
    )
    (net (code "57") (name "unconnected-(IC7-~{RI}-Pad11)") (class "Default")
      (node (ref "IC7") (pin "11") (pinfunction "~{RI}_11") (pintype "passive+no_connect"))
    )
    (net (code "58") (name "unconnected-(USB1-SBU1-PadA8)") (class "Default")
      (node (ref "USB1") (pin "A8") (pinfunction "SBU1_A8") (pintype "passive+no_connect"))
    )
    (net (code "59") (name "unconnected-(USB1-SBU2-PadB8)") (class "Default")
      (node (ref "USB1") (pin "B8") (pinfunction "SBU2_B8") (pintype "passive+no_connect"))
    )
    (net (code "60") (name "unconnected-(USB2-SBU1-PadA8)") (class "Default")
      (node (ref "USB2") (pin "A8") (pinfunction "SBU1_A8") (pintype "passive+no_connect"))
    )
    (net (code "61") (name "unconnected-(USB2-SBU2-PadB8)") (class "Default")
      (node (ref "USB2") (pin "B8") (pinfunction "SBU2_B8") (pintype "passive+no_connect"))
    )
    (net (code "62") (name "unconnected-(USB3-SBU1-PadA8)") (class "Default")
      (node (ref "USB3") (pin "A8") (pinfunction "SBU1_A8") (pintype "passive+no_connect"))
    )
    (net (code "63") (name "unconnected-(USB3-SBU2-PadB8)") (class "Default")
      (node (ref "USB3") (pin "B8") (pinfunction "SBU2_B8") (pintype "passive+no_connect"))
    )
  )
)
